# Fast_ADC_Module.net
KiCad netlist of a schematic drawn in Altium Designer
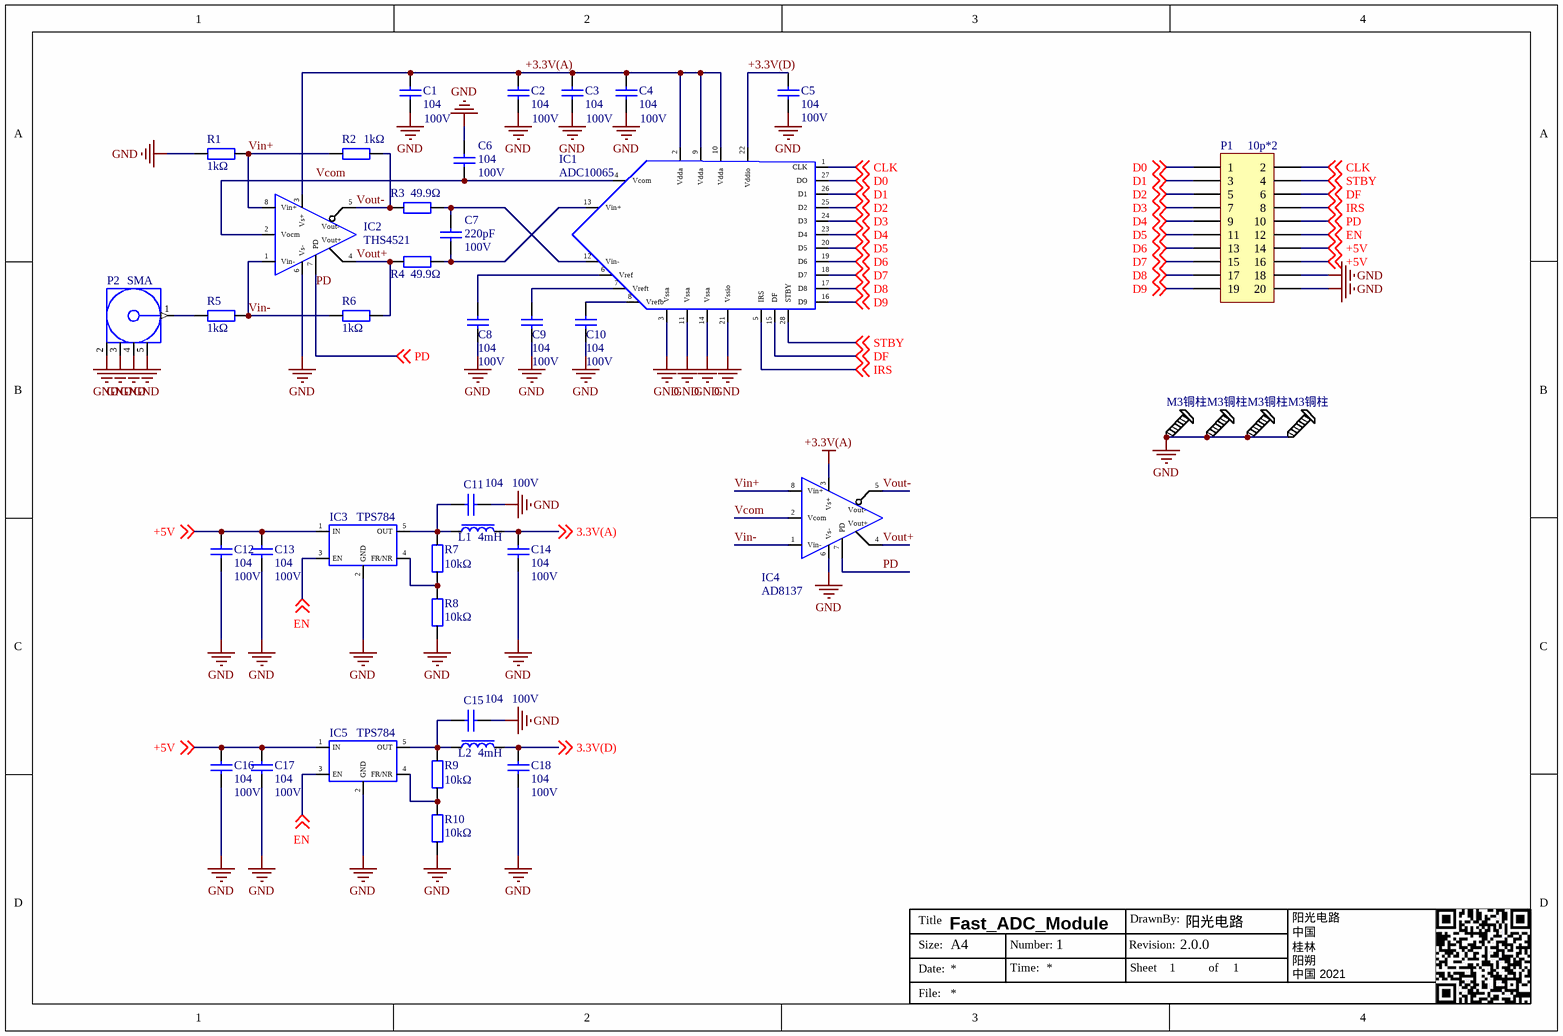
[diagram p0: Fast_ADC_Module.SchDoc]

(export (version "E")
  (design (tool "Eeschema 10.0.6"))
  (components
    (comp (ref "C1")
      (value "叠层陶瓷电容")
      (footprint "C0603")
      (description "无极性电容")
      (fields (field (name "CAPACITY") "104") (field (name "VOLTAGE") "100V"))
      (libsource (lib "原理图库") (part "104"))
    )
    (comp (ref "C2")
      (value "叠层陶瓷电容")
      (footprint "C0603")
      (description "无极性电容")
      (fields (field (name "CAPACITY") "104") (field (name "VOLTAGE") "100V"))
      (libsource (lib "原理图库") (part "104"))
    )
    (comp (ref "C3")
      (value "叠层陶瓷电容")
      (footprint "C0603")
      (description "无极性电容")
      (fields (field (name "CAPACITY") "104") (field (name "VOLTAGE") "100V"))
      (libsource (lib "原理图库") (part "104"))
    )
    (comp (ref "C4")
      (value "叠层陶瓷电容")
      (footprint "C0603")
      (description "无极性电容")
      (fields (field (name "CAPACITY") "104") (field (name "VOLTAGE") "100V"))
      (libsource (lib "原理图库") (part "104"))
    )
    (comp (ref "C5")
      (value "叠层陶瓷电容")
      (footprint "C0603")
      (description "无极性电容")
      (fields (field (name "CAPACITY") "104") (field (name "VOLTAGE") "100V"))
      (libsource (lib "原理图库") (part "104"))
    )
    (comp (ref "C6")
      (value "叠层陶瓷电容")
      (footprint "C0603")
      (description "无极性电容")
      (fields (field (name "CAPACITY") "104") (field (name "VOLTAGE") "100V"))
      (libsource (lib "原理图库") (part "104"))
    )
    (comp (ref "C7")
      (value "叠层陶瓷电容")
      (footprint "C0603")
      (description "无极性电容")
      (fields (field (name "CAPACITY") "220pF") (field (name "VOLTAGE") "100V"))
      (libsource (lib "原理图库") (part "104"))
    )
    (comp (ref "C8")
      (value "叠层陶瓷电容")
      (footprint "C0603")
      (description "无极性电容")
      (fields (field (name "CAPACITY") "104") (field (name "VOLTAGE") "100V"))
      (libsource (lib "原理图库") (part "104"))
    )
    (comp (ref "C9")
      (value "叠层陶瓷电容")
      (footprint "C0603")
      (description "无极性电容")
      (fields (field (name "CAPACITY") "104") (field (name "VOLTAGE") "100V"))
      (libsource (lib "原理图库") (part "104"))
    )
    (comp (ref "C10")
      (value "叠层陶瓷电容")
      (footprint "C0603")
      (description "无极性电容")
      (fields (field (name "CAPACITY") "104") (field (name "VOLTAGE") "100V"))
      (libsource (lib "原理图库") (part "104"))
    )
    (comp (ref "C11")
      (value "叠层陶瓷电容")
      (footprint "C0603")
      (description "无极性电容")
      (fields (field (name "CAPACITY") "104") (field (name "VOLTAGE") "100V"))
      (libsource (lib "原理图库") (part "104"))
    )
    (comp (ref "C12")
      (value "叠层陶瓷电容")
      (footprint "C0603")
      (description "无极性电容")
      (fields (field (name "CAPACITY") "104") (field (name "VOLTAGE") "100V"))
      (libsource (lib "原理图库") (part "104"))
    )
    (comp (ref "C13")
      (value "叠层陶瓷电容")
      (footprint "C0603")
      (description "无极性电容")
      (fields (field (name "CAPACITY") "104") (field (name "VOLTAGE") "100V"))
      (libsource (lib "原理图库") (part "104"))
    )
    (comp (ref "C14")
      (value "叠层陶瓷电容")
      (footprint "C0603")
      (description "无极性电容")
      (fields (field (name "CAPACITY") "104") (field (name "VOLTAGE") "100V"))
      (libsource (lib "原理图库") (part "104"))
    )
    (comp (ref "C15")
      (value "叠层陶瓷电容")
      (footprint "C0603")
      (description "无极性电容")
      (fields (field (name "CAPACITY") "104") (field (name "VOLTAGE") "100V"))
      (libsource (lib "原理图库") (part "104"))
    )
    (comp (ref "C16")
      (value "叠层陶瓷电容")
      (footprint "C0603")
      (description "无极性电容")
      (fields (field (name "CAPACITY") "104") (field (name "VOLTAGE") "100V"))
      (libsource (lib "原理图库") (part "104"))
    )
    (comp (ref "C17")
      (value "叠层陶瓷电容")
      (footprint "C0603")
      (description "无极性电容")
      (fields (field (name "CAPACITY") "104") (field (name "VOLTAGE") "100V"))
      (libsource (lib "原理图库") (part "104"))
    )
    (comp (ref "C18")
      (value "叠层陶瓷电容")
      (footprint "C0603")
      (description "无极性电容")
      (fields (field (name "CAPACITY") "104") (field (name "VOLTAGE") "100V"))
      (libsource (lib "原理图库") (part "104"))
    )
    (comp (ref "IC1")
      (value "ADC10065")
      (footprint "TSSOP-28(Wb=4.4mm、 Wl=6.4mm)")
      (description "10Bit SAR ADC  65MSPS")
      (libsource (lib "原理图库") (part "ADC10065"))
    )
    (comp (ref "IC2")
      (value "THS4521")
      (footprint "MSOP-8")
      (description "全差分运算放大器")
      (libsource (lib "原理图库") (part "THS4521"))
    )
    (comp (ref "IC3")
      (value "TSOT-23-5")
      (footprint "TSOT-23-5?")
      (description "300mA 5.5V ADJ LDO，TSOT-23-5")
      (fields (field (name "TYPE") "TPS784"))
      (libsource (lib "原理图库") (part "TPS784"))
    )
    (comp (ref "IC4")
      (value "AD8137")
      (footprint "SOP-8(体宽3.8mm)")
      (description "全差分高速运放，GBW=110MHz，电源电压2.7V~12V，SOP-8")
      (fields (field (name "TYPE") "AD8137"))
      (libsource (lib "原理图库") (part "AD8137"))
    )
    (comp (ref "IC5")
      (value "TSOT-23-5")
      (footprint "TSOT-23-5?")
      (description "300mA 5.5V ADJ LDO，TSOT-23-5")
      (fields (field (name "TYPE") "TPS784"))
      (libsource (lib "原理图库") (part "TPS784"))
    )
    (comp (ref "L1")
      (value "电感")
      (footprint "R0603")
      (fields (field (name "TYPE") "4mH"))
      (libsource (lib "原理图库") (part "470mH"))
    )
    (comp (ref "L2")
      (value "电感")
      (footprint "R0603")
      (fields (field (name "TYPE") "4mH"))
      (libsource (lib "原理图库") (part "470mH"))
    )
    (comp (ref "P1")
      (value "10p*2")
      (footprint "HDR2X10")
      (description "10p*2排针")
      (libsource (lib "Miscellaneous Connectors") (part "Header 10X2"))
    )
    (comp (ref "P2")
      (value "SMA")
      (footprint "SMA-夹板")
      (description "射频座")
      (libsource (lib "原理图库") (part "SMA"))
    )
    (comp (ref "R1")
      (value "贴片电阻")
      (footprint "R0603")
      (description "贴片/直插电阻")
      (fields (field (name "RESISTANCE") "1kΩ"))
      (libsource (lib "原理图库") (part "10kΩ"))
    )
    (comp (ref "R2")
      (value "贴片电阻")
      (footprint "R0603")
      (description "贴片/直插电阻")
      (fields (field (name "RESISTANCE") "1kΩ"))
      (libsource (lib "原理图库") (part "10kΩ"))
    )
    (comp (ref "R3")
      (value "贴片电阻")
      (footprint "R0603")
      (description "贴片/直插电阻")
      (fields (field (name "RESISTANCE") "49.9Ω"))
      (libsource (lib "原理图库") (part "10kΩ"))
    )
    (comp (ref "R4")
      (value "贴片电阻")
      (footprint "R0603")
      (description "贴片/直插电阻")
      (fields (field (name "RESISTANCE") "49.9Ω"))
      (libsource (lib "原理图库") (part "10kΩ"))
    )
    (comp (ref "R5")
      (value "贴片电阻")
      (footprint "R0603")
      (description "贴片/直插电阻")
      (fields (field (name "RESISTANCE") "1kΩ"))
      (libsource (lib "原理图库") (part "10kΩ"))
    )
    (comp (ref "R6")
      (value "贴片电阻")
      (footprint "R0603")
      (description "贴片/直插电阻")
      (fields (field (name "RESISTANCE") "1kΩ"))
      (libsource (lib "原理图库") (part "10kΩ"))
    )
    (comp (ref "R7")
      (value "贴片电阻")
      (footprint "R0603")
      (description "贴片/直插电阻")
      (fields (field (name "RESISTANCE") "10kΩ"))
      (libsource (lib "原理图库") (part "10kΩ"))
    )
    (comp (ref "R8")
      (value "贴片电阻")
      (footprint "R0603")
      (description "贴片/直插电阻")
      (fields (field (name "RESISTANCE") "10kΩ"))
      (libsource (lib "原理图库") (part "10kΩ"))
    )
    (comp (ref "R9")
      (value "贴片电阻")
      (footprint "R0603")
      (description "贴片/直插电阻")
      (fields (field (name "RESISTANCE") "10kΩ"))
      (libsource (lib "原理图库") (part "10kΩ"))
    )
    (comp (ref "R10")
      (value "贴片电阻")
      (footprint "R0603")
      (description "贴片/直插电阻")
      (fields (field (name "RESISTANCE") "10kΩ"))
      (libsource (lib "原理图库") (part "10kΩ"))
    )
    (comp (ref "S1") (value "M3铜柱") (footprint "M3") (libsource (lib "原理图库") (part "M3铜柱")))
    (comp (ref "S2") (value "M3铜柱") (footprint "M3") (libsource (lib "原理图库") (part "M3铜柱")))
    (comp (ref "S3") (value "M3铜柱") (footprint "M3") (libsource (lib "原理图库") (part "M3铜柱")))
    (comp (ref "S4") (value "M3铜柱") (footprint "M3") (libsource (lib "原理图库") (part "M3铜柱")))
  )
  (nets
    (net (code "1") (name "+3.3V(A)") (class "Default")
      (node (ref "C1") (pin "2") (pintype "passive"))
      (node (ref "C2") (pin "2") (pintype "passive"))
      (node (ref "C3") (pin "2") (pintype "passive"))
      (node (ref "C4") (pin "2") (pintype "passive"))
      (node (ref "IC1") (pin "10") (pinfunction "Vdda_10") (pintype "passive"))
      (node (ref "IC1") (pin "2") (pinfunction "Vdda_2") (pintype "passive"))
      (node (ref "IC1") (pin "9") (pinfunction "Vdda_9") (pintype "passive"))
      (node (ref "IC2") (pin "3") (pinfunction "Vs+_3") (pintype "passive"))
      (node (ref "IC4") (pin "3") (pinfunction "Vs+_3") (pintype "passive"))
    )
    (net (code "2") (name "+5V") (class "Default")
      (node (ref "C12") (pin "2") (pintype "passive"))
      (node (ref "C13") (pin "2") (pintype "passive"))
      (node (ref "C16") (pin "2") (pintype "passive"))
      (node (ref "C17") (pin "2") (pintype "passive"))
      (node (ref "IC3") (pin "1") (pinfunction "IN_1") (pintype "passive"))
      (node (ref "IC5") (pin "1") (pinfunction "IN_1") (pintype "passive"))
      (node (ref "P1") (pin "14") (pinfunction "14_14") (pintype "passive"))
      (node (ref "P1") (pin "16") (pinfunction "16_16") (pintype "passive"))
    )
    (net (code "3") (name "/+3.3V(D)") (class "Default")
      (node (ref "C5") (pin "2") (pintype "passive"))
      (node (ref "IC1") (pin "22") (pinfunction "Vddio_22") (pintype "passive"))
    )
    (net (code "4") (name "/Vcom") (class "Default")
      (node (ref "C6") (pin "1") (pintype "passive"))
      (node (ref "IC1") (pin "4") (pinfunction "Vcom_4") (pintype "passive"))
      (node (ref "IC2") (pin "2") (pinfunction "Vocm_2") (pintype "passive"))
      (node (ref "IC4") (pin "2") (pinfunction "Vcom_2") (pintype "passive"))
    )
    (net (code "5") (name "/Vin+") (class "Default")
      (node (ref "IC2") (pin "8") (pinfunction "Vin+_8") (pintype "passive"))
      (node (ref "IC4") (pin "8") (pinfunction "Vin+_8") (pintype "passive"))
      (node (ref "R1") (pin "2") (pintype "passive"))
      (node (ref "R2") (pin "1") (pintype "passive"))
    )
    (net (code "6") (name "/Vin-") (class "Default")
      (node (ref "IC2") (pin "1") (pinfunction "Vin-_1") (pintype "passive"))
      (node (ref "IC4") (pin "1") (pinfunction "Vin-_1") (pintype "passive"))
      (node (ref "R5") (pin "2") (pintype "passive"))
      (node (ref "R6") (pin "1") (pintype "passive"))
    )
    (net (code "7") (name "/Vout+") (class "Default")
      (node (ref "IC2") (pin "4") (pinfunction "Vout+_4") (pintype "passive"))
      (node (ref "IC4") (pin "4") (pinfunction "Vout+_4") (pintype "passive"))
      (node (ref "R4") (pin "1") (pintype "passive"))
      (node (ref "R6") (pin "2") (pintype "passive"))
    )
    (net (code "8") (name "/Vout-") (class "Default")
      (node (ref "IC2") (pin "5") (pinfunction "Vout-_5") (pintype "passive"))
      (node (ref "IC4") (pin "5") (pinfunction "Vout-_5") (pintype "passive"))
      (node (ref "R2") (pin "2") (pintype "passive"))
      (node (ref "R3") (pin "1") (pintype "passive"))
    )
    (net (code "9") (name "3.3V(A)") (class "Default")
      (node (ref "C14") (pin "2") (pintype "passive"))
      (node (ref "L1") (pin "1") (pintype "passive"))
    )
    (net (code "10") (name "3.3V(D)") (class "Default")
      (node (ref "C18") (pin "2") (pintype "passive"))
      (node (ref "L2") (pin "1") (pintype "passive"))
    )
    (net (code "11") (name "CLK") (class "Default")
      (node (ref "IC1") (pin "1") (pinfunction "CLK_1") (pintype "passive"))
      (node (ref "P1") (pin "2") (pinfunction "2_2") (pintype "passive"))
    )
    (net (code "12") (name "D0") (class "Default")
      (node (ref "IC1") (pin "27") (pinfunction "DO_27") (pintype "passive"))
      (node (ref "P1") (pin "1") (pinfunction "1_1") (pintype "passive"))
    )
    (net (code "13") (name "D1") (class "Default")
      (node (ref "IC1") (pin "26") (pinfunction "D1_26") (pintype "passive"))
      (node (ref "P1") (pin "3") (pinfunction "3_3") (pintype "passive"))
    )
    (net (code "14") (name "D2") (class "Default")
      (node (ref "IC1") (pin "25") (pinfunction "D2_25") (pintype "passive"))
      (node (ref "P1") (pin "5") (pinfunction "5_5") (pintype "passive"))
    )
    (net (code "15") (name "D3") (class "Default")
      (node (ref "IC1") (pin "24") (pinfunction "D3_24") (pintype "passive"))
      (node (ref "P1") (pin "7") (pinfunction "7_7") (pintype "passive"))
    )
    (net (code "16") (name "D4") (class "Default")
      (node (ref "IC1") (pin "23") (pinfunction "D4_23") (pintype "passive"))
      (node (ref "P1") (pin "9") (pinfunction "9_9") (pintype "passive"))
    )
    (net (code "17") (name "D5") (class "Default")
      (node (ref "IC1") (pin "20") (pinfunction "D5_20") (pintype "passive"))
      (node (ref "P1") (pin "11") (pinfunction "11_11") (pintype "passive"))
    )
    (net (code "18") (name "D6") (class "Default")
      (node (ref "IC1") (pin "19") (pinfunction "D6_19") (pintype "passive"))
      (node (ref "P1") (pin "13") (pinfunction "13_13") (pintype "passive"))
    )
    (net (code "19") (name "D7") (class "Default")
      (node (ref "IC1") (pin "18") (pinfunction "D7_18") (pintype "passive"))
      (node (ref "P1") (pin "15") (pinfunction "15_15") (pintype "passive"))
    )
    (net (code "20") (name "D8") (class "Default")
      (node (ref "IC1") (pin "17") (pinfunction "D8_17") (pintype "passive"))
      (node (ref "P1") (pin "17") (pinfunction "17_17") (pintype "passive"))
    )
    (net (code "21") (name "D9") (class "Default")
      (node (ref "IC1") (pin "16") (pinfunction "D9_16") (pintype "passive"))
      (node (ref "P1") (pin "19") (pinfunction "19_19") (pintype "passive"))
    )
    (net (code "22") (name "DF") (class "Default")
      (node (ref "IC1") (pin "15") (pinfunction "DF_15") (pintype "passive"))
      (node (ref "P1") (pin "6") (pinfunction "6_6") (pintype "passive"))
    )
    (net (code "23") (name "EN") (class "Default")
      (node (ref "IC3") (pin "3") (pinfunction "EN_3") (pintype "passive"))
      (node (ref "IC5") (pin "3") (pinfunction "EN_3") (pintype "passive"))
      (node (ref "P1") (pin "12") (pinfunction "12_12") (pintype "passive"))
    )
    (net (code "24") (name "GND") (class "Default")
      (node (ref "C1") (pin "1") (pintype "passive"))
      (node (ref "C10") (pin "1") (pintype "passive"))
      (node (ref "C11") (pin "1") (pintype "passive"))
      (node (ref "C12") (pin "1") (pintype "passive"))
      (node (ref "C13") (pin "1") (pintype "passive"))
      (node (ref "C14") (pin "1") (pintype "passive"))
      (node (ref "C15") (pin "1") (pintype "passive"))
      (node (ref "C16") (pin "1") (pintype "passive"))
      (node (ref "C17") (pin "1") (pintype "passive"))
      (node (ref "C18") (pin "1") (pintype "passive"))
      (node (ref "C2") (pin "1") (pintype "passive"))
      (node (ref "C3") (pin "1") (pintype "passive"))
      (node (ref "C4") (pin "1") (pintype "passive"))
      (node (ref "C5") (pin "1") (pintype "passive"))
      (node (ref "C6") (pin "2") (pintype "passive"))
      (node (ref "C8") (pin "1") (pintype "passive"))
      (node (ref "C9") (pin "1") (pintype "passive"))
      (node (ref "IC1") (pin "11") (pinfunction "Vssa_11") (pintype "passive"))
      (node (ref "IC1") (pin "14") (pinfunction "Vssa_14") (pintype "passive"))
      (node (ref "IC1") (pin "21") (pinfunction "Vssio_21") (pintype "passive"))
      (node (ref "IC1") (pin "3") (pinfunction "Vssa_3") (pintype "passive"))
      (node (ref "IC2") (pin "6") (pinfunction "Vs-_6") (pintype "passive"))
      (node (ref "IC3") (pin "2") (pinfunction "GND_2") (pintype "passive"))
      (node (ref "IC4") (pin "6") (pinfunction "Vs-_6") (pintype "passive"))
      (node (ref "IC5") (pin "2") (pinfunction "GND_2") (pintype "passive"))
      (node (ref "P1") (pin "18") (pinfunction "18_18") (pintype "passive"))
      (node (ref "P1") (pin "20") (pinfunction "20_20") (pintype "passive"))
      (node (ref "P2") (pin "2") (pinfunction "2_2") (pintype "passive"))
      (node (ref "P2") (pin "3") (pinfunction "3_3") (pintype "passive"))
      (node (ref "P2") (pin "4") (pinfunction "4_4") (pintype "passive"))
      (node (ref "P2") (pin "5") (pinfunction "5_5") (pintype "passive"))
      (node (ref "R1") (pin "1") (pintype "passive"))
      (node (ref "R10") (pin "1") (pintype "passive"))
      (node (ref "R8") (pin "1") (pintype "passive"))
      (node (ref "S1") (pin "1") (pinfunction "GND_1") (pintype "passive"))
      (node (ref "S2") (pin "1") (pinfunction "GND_1") (pintype "passive"))
      (node (ref "S3") (pin "1") (pinfunction "GND_1") (pintype "passive"))
      (node (ref "S4") (pin "1") (pinfunction "GND_1") (pintype "passive"))
    )
    (net (code "25") (name "IRS") (class "Default")
      (node (ref "IC1") (pin "5") (pinfunction "IRS_5") (pintype "passive"))
      (node (ref "P1") (pin "8") (pinfunction "8_8") (pintype "passive"))
    )
    (net (code "26") (name "Net-(IC1-Vin+)") (class "Default")
      (node (ref "C7") (pin "1") (pintype "passive"))
      (node (ref "IC1") (pin "13") (pinfunction "Vin+_13") (pintype "passive"))
      (node (ref "R4") (pin "2") (pintype "passive"))
    )
    (net (code "27") (name "Net-(IC1-Vin-)") (class "Default")
      (node (ref "C7") (pin "2") (pintype "passive"))
      (node (ref "IC1") (pin "12") (pinfunction "Vin-_12") (pintype "passive"))
      (node (ref "R3") (pin "2") (pintype "passive"))
    )
    (net (code "28") (name "Net-(IC1-Vref)") (class "Default")
      (node (ref "C8") (pin "2") (pintype "passive"))
      (node (ref "IC1") (pin "6") (pinfunction "Vref_6") (pintype "passive"))
    )
    (net (code "29") (name "Net-(IC1-Vrefb)") (class "Default")
      (node (ref "C10") (pin "2") (pintype "passive"))
      (node (ref "IC1") (pin "8") (pinfunction "Vrefb_8") (pintype "passive"))
    )
    (net (code "30") (name "Net-(IC1-Vreft)") (class "Default")
      (node (ref "C9") (pin "2") (pintype "passive"))
      (node (ref "IC1") (pin "7") (pinfunction "Vreft_7") (pintype "passive"))
    )
    (net (code "31") (name "Net-(IC3-FR{slash}NR)") (class "Default")
      (node (ref "IC3") (pin "4") (pinfunction "FR/NR_4") (pintype "passive"))
      (node (ref "R7") (pin "1") (pintype "passive"))
      (node (ref "R8") (pin "2") (pintype "passive"))
    )
    (net (code "32") (name "Net-(IC3-OUT)") (class "Default")
      (node (ref "C11") (pin "2") (pintype "passive"))
      (node (ref "IC3") (pin "5") (pinfunction "OUT_5") (pintype "passive"))
      (node (ref "L1") (pin "2") (pintype "passive"))
      (node (ref "R7") (pin "2") (pintype "passive"))
    )
    (net (code "33") (name "Net-(IC5-FR{slash}NR)") (class "Default")
      (node (ref "IC5") (pin "4") (pinfunction "FR/NR_4") (pintype "passive"))
      (node (ref "R10") (pin "2") (pintype "passive"))
      (node (ref "R9") (pin "1") (pintype "passive"))
    )
    (net (code "34") (name "Net-(IC5-OUT)") (class "Default")
      (node (ref "C15") (pin "2") (pintype "passive"))
      (node (ref "IC5") (pin "5") (pinfunction "OUT_5") (pintype "passive"))
      (node (ref "L2") (pin "2") (pintype "passive"))
      (node (ref "R9") (pin "2") (pintype "passive"))
    )
    (net (code "35") (name "Net-(P2-Pad1)") (class "Default")
      (node (ref "P2") (pin "1") (pinfunction "1_1") (pintype "output"))
      (node (ref "R5") (pin "1") (pintype "passive"))
    )
    (net (code "36") (name "PD") (class "Default")
      (node (ref "IC2") (pin "7") (pinfunction "PD_7") (pintype "passive"))
      (node (ref "IC4") (pin "7") (pinfunction "PD_7") (pintype "passive"))
      (node (ref "P1") (pin "10") (pinfunction "10_10") (pintype "passive"))
    )
    (net (code "37") (name "STBY") (class "Default")
      (node (ref "IC1") (pin "28") (pinfunction "STBY_28") (pintype "passive"))
      (node (ref "P1") (pin "4") (pinfunction "4_4") (pintype "passive"))
    )
  )
)
